# bigger_board.net
KiCad netlist of a schematic drawn in EAGLE
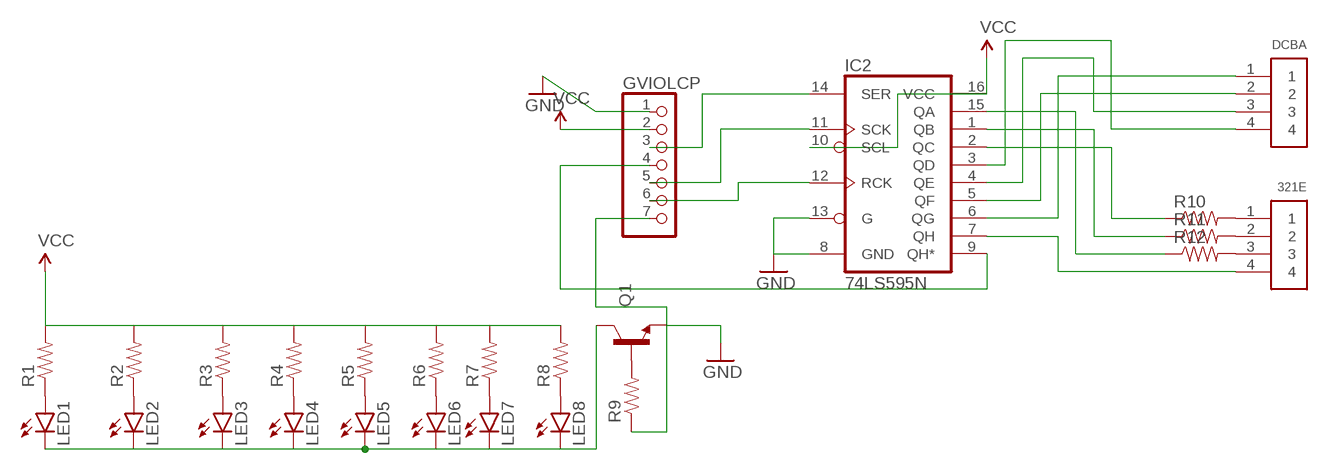
[diagram p0: schematic, sheet 1]

(export (version "E")
  (design (tool "Eeschema 10.0.6"))
  (components
    (comp (ref "321E")
      (value "1X4-BIG")
      (footprint "eagle-import:1X04-BIG")
      (libsource (lib "eagle-import") (part "1X4-BIG"))
    )
    (comp (ref "DCBA")
      (value "1X4-BIG")
      (footprint "eagle-import:1X04-BIG")
      (libsource (lib "eagle-import") (part "1X4-BIG"))
    )
    (comp (ref "GVIOLCP")
      (value "PINHD-1X7")
      (footprint "eagle-import:1X07")
      (libsource (lib "eagle-import") (part "PINHD-1X7"))
    )
    (comp (ref "IC2")
      (value "74LS595N")
      (footprint "eagle-import:DIL16")
      (libsource (lib "eagle-import") (part "74595NLS"))
    )
    (comp (ref "LED1")
      (value "LED3MM")
      (footprint "eagle-import:LED3MM")
      (libsource (lib "eagle-import") (part "LED3MM"))
    )
    (comp (ref "LED2")
      (value "LED3MM")
      (footprint "eagle-import:LED3MM")
      (libsource (lib "eagle-import") (part "LED3MM"))
    )
    (comp (ref "LED3")
      (value "LED3MM")
      (footprint "eagle-import:LED3MM")
      (libsource (lib "eagle-import") (part "LED3MM"))
    )
    (comp (ref "LED4")
      (value "LED3MM")
      (footprint "eagle-import:LED3MM")
      (libsource (lib "eagle-import") (part "LED3MM"))
    )
    (comp (ref "LED5")
      (value "LED3MM")
      (footprint "eagle-import:LED3MM")
      (libsource (lib "eagle-import") (part "LED3MM"))
    )
    (comp (ref "LED6")
      (value "LED3MM")
      (footprint "eagle-import:LED3MM")
      (libsource (lib "eagle-import") (part "LED3MM"))
    )
    (comp (ref "LED7")
      (value "LED3MM")
      (footprint "eagle-import:LED3MM")
      (libsource (lib "eagle-import") (part "LED3MM"))
    )
    (comp (ref "LED8")
      (value "LED3MM")
      (footprint "eagle-import:LED3MM")
      (libsource (lib "eagle-import") (part "LED3MM"))
    )
    (comp (ref "Q1")
      (value "TRANSISTOR_NPNBC547")
      (footprint "eagle-import:TO-92-AMMO")
      (libsource (lib "eagle-import") (part "TRANSISTOR_NPNBC547"))
    )
    (comp (ref "R1")
      (value "RESISTOR1206")
      (footprint "eagle-import:1206")
      (libsource (lib "eagle-import") (part "RESISTOR1206"))
    )
    (comp (ref "R2")
      (value "RESISTOR1206")
      (footprint "eagle-import:1206")
      (libsource (lib "eagle-import") (part "RESISTOR1206"))
    )
    (comp (ref "R3")
      (value "RESISTOR1206")
      (footprint "eagle-import:1206")
      (libsource (lib "eagle-import") (part "RESISTOR1206"))
    )
    (comp (ref "R4")
      (value "RESISTOR1206")
      (footprint "eagle-import:1206")
      (libsource (lib "eagle-import") (part "RESISTOR1206"))
    )
    (comp (ref "R5")
      (value "RESISTOR1206")
      (footprint "eagle-import:1206")
      (libsource (lib "eagle-import") (part "RESISTOR1206"))
    )
    (comp (ref "R6")
      (value "RESISTOR1206")
      (footprint "eagle-import:1206")
      (libsource (lib "eagle-import") (part "RESISTOR1206"))
    )
    (comp (ref "R7")
      (value "RESISTOR1206")
      (footprint "eagle-import:1206")
      (libsource (lib "eagle-import") (part "RESISTOR1206"))
    )
    (comp (ref "R8")
      (value "RESISTOR1206")
      (footprint "eagle-import:1206")
      (libsource (lib "eagle-import") (part "RESISTOR1206"))
    )
    (comp (ref "R9")
      (value "RESISTOR1206")
      (footprint "eagle-import:1206")
      (libsource (lib "eagle-import") (part "RESISTOR1206"))
    )
    (comp (ref "R10")
      (value "RESISTOR1206")
      (footprint "eagle-import:1206")
      (libsource (lib "eagle-import") (part "RESISTOR1206"))
    )
    (comp (ref "R11")
      (value "RESISTOR1206")
      (footprint "eagle-import:1206")
      (libsource (lib "eagle-import") (part "RESISTOR1206"))
    )
    (comp (ref "R12")
      (value "RESISTOR1206")
      (footprint "eagle-import:1206")
      (libsource (lib "eagle-import") (part "RESISTOR1206"))
    )
  )
  (nets
    (net (code "1") (name "GND") (class "Default")
      (node (ref "GVIOLCP") (pin "1") (pinfunction "1_1") (pintype "passive"))
      (node (ref "IC2") (pin "13") (pinfunction "G_13") (pintype "input"))
      (node (ref "IC2") (pin "8") (pinfunction "GND_8") (pintype "power_in"))
      (node (ref "Q1") (pin "3") (pinfunction "E_3") (pintype "passive"))
    )
    (net (code "2") (name "Net-(321E-Pad1)") (class "Default")
      (node (ref "321E") (pin "1") (pinfunction "1_1") (pintype "bidirectional"))
      (node (ref "R10") (pin "2") (pinfunction "2_2") (pintype "passive"))
    )
    (net (code "3") (name "Net-(321E-Pad2)") (class "Default")
      (node (ref "321E") (pin "2") (pinfunction "2_2") (pintype "bidirectional"))
      (node (ref "R11") (pin "2") (pinfunction "2_2") (pintype "passive"))
    )
    (net (code "4") (name "Net-(321E-Pad3)") (class "Default")
      (node (ref "321E") (pin "3") (pinfunction "3_3") (pintype "bidirectional"))
      (node (ref "R12") (pin "2") (pinfunction "2_2") (pintype "passive"))
    )
    (net (code "5") (name "Net-(GVIOLCP-Pad7)") (class "Default")
      (node (ref "GVIOLCP") (pin "7") (pinfunction "7_7") (pintype "passive"))
      (node (ref "R9") (pin "1") (pinfunction "1_1") (pintype "passive"))
    )
    (net (code "6") (name "Net-(IC2-QA)") (class "Default")
      (node (ref "IC2") (pin "15") (pinfunction "QA_15") (pintype "tri_state"))
      (node (ref "R12") (pin "1") (pinfunction "1_1") (pintype "passive"))
    )
    (net (code "7") (name "Net-(IC2-QB)") (class "Default")
      (node (ref "IC2") (pin "1") (pinfunction "QB_1") (pintype "tri_state"))
      (node (ref "R11") (pin "1") (pinfunction "1_1") (pintype "passive"))
    )
    (net (code "8") (name "Net-(IC2-QC)") (class "Default")
      (node (ref "IC2") (pin "2") (pinfunction "QC_2") (pintype "tri_state"))
      (node (ref "R10") (pin "1") (pinfunction "1_1") (pintype "passive"))
    )
    (net (code "9") (name "Net-(IC2-QD)") (class "Default")
      (node (ref "DCBA") (pin "4") (pinfunction "4_4") (pintype "bidirectional"))
      (node (ref "IC2") (pin "3") (pinfunction "QD_3") (pintype "tri_state"))
    )
    (net (code "10") (name "Net-(IC2-QE)") (class "Default")
      (node (ref "DCBA") (pin "3") (pinfunction "3_3") (pintype "bidirectional"))
      (node (ref "IC2") (pin "4") (pinfunction "QE_4") (pintype "tri_state"))
    )
    (net (code "11") (name "Net-(IC2-QF)") (class "Default")
      (node (ref "DCBA") (pin "2") (pinfunction "2_2") (pintype "bidirectional"))
      (node (ref "IC2") (pin "5") (pinfunction "QF_5") (pintype "tri_state"))
    )
    (net (code "12") (name "Net-(IC2-QG)") (class "Default")
      (node (ref "DCBA") (pin "1") (pinfunction "1_1") (pintype "bidirectional"))
      (node (ref "IC2") (pin "6") (pinfunction "QG_6") (pintype "tri_state"))
    )
    (net (code "13") (name "Net-(IC2-QH)") (class "Default")
      (node (ref "321E") (pin "4") (pinfunction "4_4") (pintype "bidirectional"))
      (node (ref "IC2") (pin "7") (pinfunction "QH_7") (pintype "tri_state"))
    )
    (net (code "14") (name "Net-(IC2-QH*)") (class "Default")
      (node (ref "GVIOLCP") (pin "4") (pinfunction "4_4") (pintype "passive"))
      (node (ref "IC2") (pin "9") (pinfunction "QH*_9") (pintype "tri_state"))
    )
    (net (code "15") (name "Net-(IC2-RCK)") (class "Default")
      (node (ref "GVIOLCP") (pin "6") (pinfunction "6_6") (pintype "passive"))
      (node (ref "IC2") (pin "12") (pinfunction "RCK_12") (pintype "input"))
    )
    (net (code "16") (name "Net-(IC2-SCK)") (class "Default")
      (node (ref "GVIOLCP") (pin "5") (pinfunction "5_5") (pintype "passive"))
      (node (ref "IC2") (pin "11") (pinfunction "SCK_11") (pintype "input"))
    )
    (net (code "17") (name "Net-(IC2-SER)") (class "Default")
      (node (ref "GVIOLCP") (pin "3") (pinfunction "3_3") (pintype "passive"))
      (node (ref "IC2") (pin "14") (pinfunction "SER_14") (pintype "input"))
    )
    (net (code "18") (name "Net-(LED1-C)") (class "Default")
      (node (ref "LED1") (pin "K") (pinfunction "C_K") (pintype "passive"))
      (node (ref "LED2") (pin "K") (pinfunction "C_K") (pintype "passive"))
      (node (ref "LED3") (pin "K") (pinfunction "C_K") (pintype "passive"))
      (node (ref "LED4") (pin "K") (pinfunction "C_K") (pintype "passive"))
      (node (ref "LED5") (pin "K") (pinfunction "C_K") (pintype "passive"))
      (node (ref "LED6") (pin "K") (pinfunction "C_K") (pintype "passive"))
      (node (ref "LED7") (pin "K") (pinfunction "C_K") (pintype "passive"))
      (node (ref "LED8") (pin "K") (pinfunction "C_K") (pintype "passive"))
      (node (ref "Q1") (pin "1") (pinfunction "C_1") (pintype "passive"))
    )
    (net (code "19") (name "Net-(LED1-PadA)") (class "Default")
      (node (ref "LED1") (pin "A") (pinfunction "A_A") (pintype "passive"))
      (node (ref "R1") (pin "1") (pinfunction "1_1") (pintype "passive"))
    )
    (net (code "20") (name "Net-(LED2-PadA)") (class "Default")
      (node (ref "LED2") (pin "A") (pinfunction "A_A") (pintype "passive"))
      (node (ref "R2") (pin "1") (pinfunction "1_1") (pintype "passive"))
    )
    (net (code "21") (name "Net-(LED3-PadA)") (class "Default")
      (node (ref "LED3") (pin "A") (pinfunction "A_A") (pintype "passive"))
      (node (ref "R3") (pin "1") (pinfunction "1_1") (pintype "passive"))
    )
    (net (code "22") (name "Net-(LED4-PadA)") (class "Default")
      (node (ref "LED4") (pin "A") (pinfunction "A_A") (pintype "passive"))
      (node (ref "R4") (pin "1") (pinfunction "1_1") (pintype "passive"))
    )
    (net (code "23") (name "Net-(LED5-PadA)") (class "Default")
      (node (ref "LED5") (pin "A") (pinfunction "A_A") (pintype "passive"))
      (node (ref "R5") (pin "1") (pinfunction "1_1") (pintype "passive"))
    )
    (net (code "24") (name "Net-(LED6-PadA)") (class "Default")
      (node (ref "LED6") (pin "A") (pinfunction "A_A") (pintype "passive"))
      (node (ref "R6") (pin "1") (pinfunction "1_1") (pintype "passive"))
    )
    (net (code "25") (name "Net-(LED7-PadA)") (class "Default")
      (node (ref "LED7") (pin "A") (pinfunction "A_A") (pintype "passive"))
      (node (ref "R7") (pin "1") (pinfunction "1_1") (pintype "passive"))
    )
    (net (code "26") (name "Net-(LED8-PadA)") (class "Default")
      (node (ref "LED8") (pin "A") (pinfunction "A_A") (pintype "passive"))
      (node (ref "R8") (pin "1") (pinfunction "1_1") (pintype "passive"))
    )
    (net (code "27") (name "Net-(Q1-B)") (class "Default")
      (node (ref "Q1") (pin "2") (pinfunction "B_2") (pintype "passive"))
      (node (ref "R9") (pin "2") (pinfunction "2_2") (pintype "passive"))
    )
    (net (code "28") (name "VCC") (class "Default")
      (node (ref "GVIOLCP") (pin "2") (pinfunction "2_2") (pintype "passive"))
      (node (ref "IC2") (pin "10") (pinfunction "SCL_10") (pintype "input"))
      (node (ref "IC2") (pin "16") (pinfunction "VCC_16") (pintype "power_in"))
      (node (ref "R1") (pin "2") (pinfunction "2_2") (pintype "passive"))
      (node (ref "R2") (pin "2") (pinfunction "2_2") (pintype "passive"))
      (node (ref "R3") (pin "2") (pinfunction "2_2") (pintype "passive"))
      (node (ref "R4") (pin "2") (pinfunction "2_2") (pintype "passive"))
      (node (ref "R5") (pin "2") (pinfunction "2_2") (pintype "passive"))
      (node (ref "R6") (pin "2") (pinfunction "2_2") (pintype "passive"))
      (node (ref "R7") (pin "2") (pinfunction "2_2") (pintype "passive"))
      (node (ref "R8") (pin "2") (pinfunction "2_2") (pintype "passive"))
    )
  )
)
